# MCU.net
KiCad netlist of a schematic drawn in Altium Designer
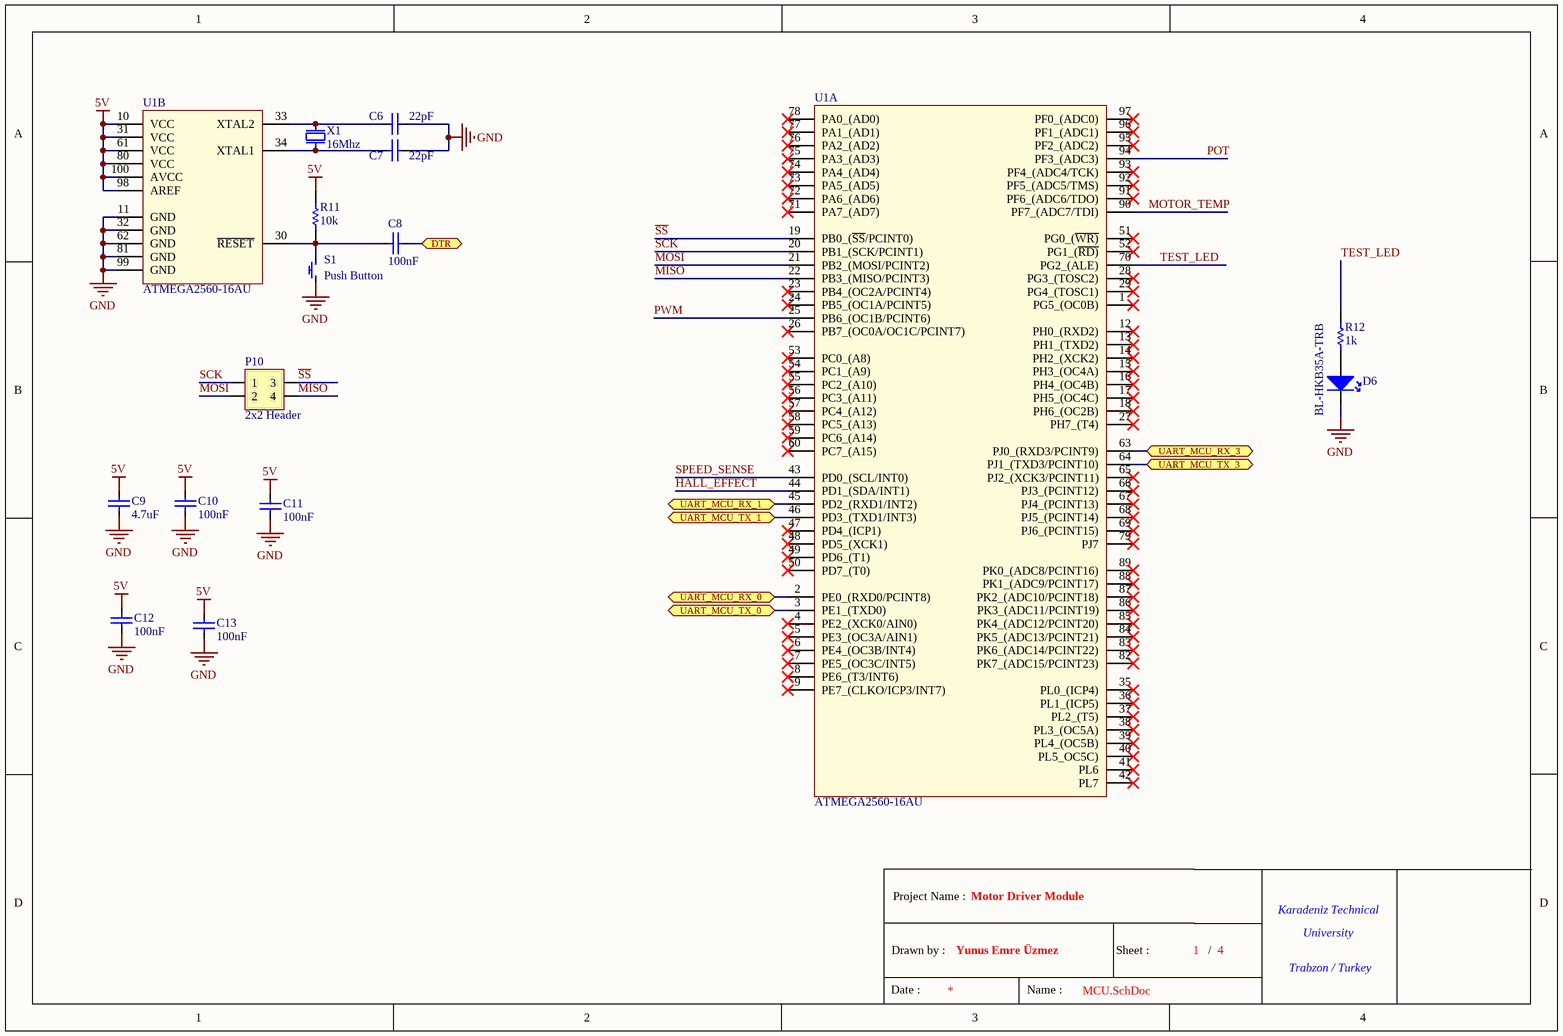
[diagram p0: MCU.SchDoc]

(export (version "E")
  (design (tool "Eeschema 10.0.6"))
  (components
    (comp (ref "C6")
      (value "22pF")
      (footprint "CAP-0805")
      (fields
        (field (name "MANUFACTURER") "Samsung Electro-Mechanics")
        (field (name "VOLTAGE") "50V")
        (field (name "TOLERANCE") "%5")
      )
      (libsource (lib "My_Libs") (part "CL21C220JBANNNC"))
    )
    (comp (ref "C7")
      (value "22pF")
      (footprint "CAP-0805")
      (fields
        (field (name "MANUFACTURER") "Samsung Electro-Mechanics")
        (field (name "VOLTAGE") "50V")
        (field (name "TOLERANCE") "%5")
      )
      (libsource (lib "My_Libs") (part "CL21C220JBANNNC"))
    )
    (comp (ref "C8")
      (value "100nF")
      (footprint "CAP-0603")
      (fields
        (field (name "MANUFACTURER") "TDK")
        (field (name "VOLTAGE") "50V")
        (field (name "TOLERANCE") "%10")
      )
      (libsource (lib "My_Libs") (part "CGA3E2X7R1H104K080AA"))
    )
    (comp (ref "C9")
      (value "4.7uF")
      (footprint "CAP-0805")
      (fields
        (field (name "MANUFACTURER") "Kemet")
        (field (name "VOLTAGE") "25V")
        (field (name "TOLERANCE") "%10")
      )
      (libsource (lib "My_Libs") (part "C0805C475K3RACAUTO"))
    )
    (comp (ref "C10")
      (value "100nF")
      (footprint "CAP-0603")
      (fields
        (field (name "MANUFACTURER") "TDK")
        (field (name "VOLTAGE") "50V")
        (field (name "TOLERANCE") "%10")
      )
      (libsource (lib "My_Libs") (part "CGA3E2X7R1H104K080AA"))
    )
    (comp (ref "C11")
      (value "100nF")
      (footprint "CAP-0603")
      (fields
        (field (name "MANUFACTURER") "TDK")
        (field (name "VOLTAGE") "50V")
        (field (name "TOLERANCE") "%10")
      )
      (libsource (lib "My_Libs") (part "CGA3E2X7R1H104K080AA"))
    )
    (comp (ref "C12")
      (value "100nF")
      (footprint "CAP-0603")
      (fields
        (field (name "MANUFACTURER") "TDK")
        (field (name "VOLTAGE") "50V")
        (field (name "TOLERANCE") "%10")
      )
      (libsource (lib "My_Libs") (part "CGA3E2X7R1H104K080AA"))
    )
    (comp (ref "C13")
      (value "100nF")
      (footprint "CAP-0603")
      (fields
        (field (name "MANUFACTURER") "TDK")
        (field (name "VOLTAGE") "50V")
        (field (name "TOLERANCE") "%10")
      )
      (libsource (lib "My_Libs") (part "CGA3E2X7R1H104K080AA"))
    )
    (comp (ref "D6")
      (value "BL-HKB35A-TRB")
      (footprint "LED-0805")
      (fields (field (name "MANUFACTURER") "BRIGHT LED"))
      (libsource (lib "My_Libs") (part "BL-HKB35A-TRB"))
    )
    (comp (ref "P10")
      (value "2x2 Header")
      (footprint "2x2 Header (2.54mm)")
      (libsource (lib "My_Libs") (part "2x2 Header (2.54mm)"))
    )
    (comp (ref "R11")
      (value "10k")
      (footprint "RES-0603")
      (fields
        (field (name "MANUFACTURER") "Vishay")
        (field (name "TOLERANCE") "%1")
        (field (name "POWER") "0.1W")
      )
      (libsource (lib "My_Libs") (part "CRCW060310K0FKEA"))
    )
    (comp (ref "R12")
      (value "1k")
      (footprint "RES-0603")
      (fields
        (field (name "MANUFACTURER") "Vishay")
        (field (name "TOLERANCE") "%1")
        (field (name "POWER") "0.1W")
      )
      (libsource (lib "My_Libs") (part "CRCW06031K00FKEAC"))
    )
    (comp (ref "S1")
      (value "Push Button")
      (footprint "2.54mm_Push Button")
      (libsource (lib "My_Libs") (part "Push Button"))
    )
    (comp (ref "U1")
      (value "ATMEGA2560-16AU")
      (footprint "Motor_Driver:TQFP-100 Microchip")
      (fields (field (name "MANUFACTURER") "Microchip"))
      (libsource (lib "My_Libs") (part "ATMEGA2560-16AU"))
    )
    (comp (ref "X1")
      (value "16Mhz")
      (footprint "OSC-THT (11.5*5.00*3.60)")
      (fields (field (name "MANUFACTURER") "ANSEN"))
      (libsource (lib "My_Libs") (part "AS49S-16M-FC160F3"))
    )
  )
  (nets
    (net (code "1") (name "/DTR") (class "Default")
      (node (ref "C8") (pin "2") (pinfunction "2_2") (pintype "passive"))
    )
    (net (code "2") (name "/HALL_EFFECT") (class "Default")
      (node (ref "U1") (pin "44") (pinfunction "PD1_(SDA/INT1)_44") (pintype "passive"))
    )
    (net (code "3") (name "/MISO") (class "Default")
      (node (ref "P10") (pin "4") (pinfunction "4_4") (pintype "passive"))
      (node (ref "U1") (pin "22") (pinfunction "PB3_(MISO/PCINT3)_22") (pintype "passive"))
    )
    (net (code "4") (name "/MOSI") (class "Default")
      (node (ref "P10") (pin "2") (pinfunction "2_2") (pintype "passive"))
      (node (ref "U1") (pin "21") (pinfunction "PB2_(MOSI/PCINT2)_21") (pintype "passive"))
    )
    (net (code "5") (name "/MOTOR_TEMP") (class "Default")
      (node (ref "U1") (pin "90") (pinfunction "PF7_(ADC7/TDI)_90") (pintype "passive"))
    )
    (net (code "6") (name "/POT") (class "Default")
      (node (ref "U1") (pin "94") (pinfunction "PF3_(ADC3)_94") (pintype "passive"))
    )
    (net (code "7") (name "/PWM") (class "Default")
      (node (ref "U1") (pin "25") (pinfunction "PB6_(OC1B/PCINT6)_25") (pintype "passive"))
    )
    (net (code "8") (name "/SCK") (class "Default")
      (node (ref "P10") (pin "1") (pinfunction "1_1") (pintype "passive"))
      (node (ref "U1") (pin "20") (pinfunction "PB1_(SCK/PCINT1)_20") (pintype "passive"))
    )
    (net (code "9") (name "/SPEED_SENSE") (class "Default")
      (node (ref "U1") (pin "43") (pinfunction "PD0_(SCL/INT0)_43") (pintype "passive"))
    )
    (net (code "10") (name "/TEST_LED") (class "Default")
      (node (ref "R12") (pin "2") (pinfunction "2_2") (pintype "passive"))
      (node (ref "U1") (pin "70") (pinfunction "PG2_(ALE)_70") (pintype "passive"))
    )
    (net (code "11") (name "/UART_MCU_RX_0") (class "Default")
      (node (ref "U1") (pin "2") (pinfunction "PE0_(RXD0/PCINT8)_2") (pintype "passive"))
    )
    (net (code "12") (name "/UART_MCU_RX_1") (class "Default")
      (node (ref "U1") (pin "45") (pinfunction "PD2_(RXD1/INT2)_45") (pintype "passive"))
    )
    (net (code "13") (name "/UART_MCU_RX_3") (class "Default")
      (node (ref "U1") (pin "63") (pinfunction "PJ0_(RXD3/PCINT9)_63") (pintype "passive"))
    )
    (net (code "14") (name "/UART_MCU_TX_0") (class "Default")
      (node (ref "U1") (pin "3") (pinfunction "PE1_(TXD0)_3") (pintype "passive"))
    )
    (net (code "15") (name "/UART_MCU_TX_1") (class "Default")
      (node (ref "U1") (pin "46") (pinfunction "PD3_(TXD1/INT3)_46") (pintype "passive"))
    )
    (net (code "16") (name "/UART_MCU_TX_3") (class "Default")
      (node (ref "U1") (pin "64") (pinfunction "PJ1_(TXD3/PCINT10)_64") (pintype "passive"))
    )
    (net (code "17") (name "/~{SS}") (class "Default")
      (node (ref "P10") (pin "3") (pinfunction "3_3") (pintype "passive"))
      (node (ref "U1") (pin "19") (pinfunction "PB0_(~{SS}/PCINT0)_19") (pintype "passive"))
    )
    (net (code "18") (name "5V") (class "Default")
      (node (ref "C10") (pin "2") (pinfunction "2_2") (pintype "passive"))
      (node (ref "C11") (pin "2") (pinfunction "2_2") (pintype "passive"))
      (node (ref "C12") (pin "2") (pinfunction "2_2") (pintype "passive"))
      (node (ref "C13") (pin "2") (pinfunction "2_2") (pintype "passive"))
      (node (ref "C9") (pin "2") (pinfunction "2_2") (pintype "passive"))
      (node (ref "R11") (pin "2") (pinfunction "2_2") (pintype "passive"))
      (node (ref "U1") (pin "10") (pinfunction "VCC_10") (pintype "passive"))
      (node (ref "U1") (pin "100") (pinfunction "AVCC_100") (pintype "passive"))
      (node (ref "U1") (pin "31") (pinfunction "VCC_31") (pintype "passive"))
      (node (ref "U1") (pin "61") (pinfunction "VCC_61") (pintype "passive"))
      (node (ref "U1") (pin "80") (pinfunction "VCC_80") (pintype "passive"))
      (node (ref "U1") (pin "98") (pinfunction "AREF_98") (pintype "passive"))
    )
    (net (code "19") (name "GND") (class "Default")
      (node (ref "C10") (pin "1") (pinfunction "1_1") (pintype "passive"))
      (node (ref "C11") (pin "1") (pinfunction "1_1") (pintype "passive"))
      (node (ref "C12") (pin "1") (pinfunction "1_1") (pintype "passive"))
      (node (ref "C13") (pin "1") (pinfunction "1_1") (pintype "passive"))
      (node (ref "C6") (pin "1") (pinfunction "1_1") (pintype "passive"))
      (node (ref "C7") (pin "1") (pinfunction "1_1") (pintype "passive"))
      (node (ref "C9") (pin "1") (pinfunction "1_1") (pintype "passive"))
      (node (ref "D6") (pin "2") (pinfunction "K_2") (pintype "passive"))
      (node (ref "S1") (pin "1") (pinfunction "1_1") (pintype "passive"))
      (node (ref "U1") (pin "11") (pinfunction "GND_11") (pintype "passive"))
      (node (ref "U1") (pin "32") (pinfunction "GND_32") (pintype "passive"))
      (node (ref "U1") (pin "62") (pinfunction "GND_62") (pintype "passive"))
      (node (ref "U1") (pin "81") (pinfunction "GND_81") (pintype "passive"))
      (node (ref "U1") (pin "99") (pinfunction "GND_99") (pintype "passive"))
    )
    (net (code "20") (name "Net-(D6-A)") (class "Default")
      (node (ref "D6") (pin "1") (pinfunction "A_1") (pintype "passive"))
      (node (ref "R12") (pin "1") (pinfunction "1_1") (pintype "passive"))
    )
    (net (code "21") (name "Net-(U1B-XTAL1)") (class "Default")
      (node (ref "C7") (pin "2") (pinfunction "2_2") (pintype "passive"))
      (node (ref "U1") (pin "34") (pinfunction "XTAL1_34") (pintype "passive"))
      (node (ref "X1") (pin "1") (pinfunction "1_1") (pintype "passive"))
    )
    (net (code "22") (name "Net-(U1B-XTAL2)") (class "Default")
      (node (ref "C6") (pin "2") (pinfunction "2_2") (pintype "passive"))
      (node (ref "U1") (pin "33") (pinfunction "XTAL2_33") (pintype "passive"))
      (node (ref "X1") (pin "2") (pinfunction "2_2") (pintype "passive"))
    )
    (net (code "23") (name "Net-(U1B-~{RESET})") (class "Default")
      (node (ref "C8") (pin "1") (pinfunction "1_1") (pintype "passive"))
      (node (ref "R11") (pin "1") (pinfunction "1_1") (pintype "passive"))
      (node (ref "S1") (pin "2") (pinfunction "2_2") (pintype "passive"))
      (node (ref "U1") (pin "30") (pinfunction "~{RESET}_30") (pintype "passive"))
    )
    (net (code "24") (name "unconnected-(U1A-PA0_(AD0)-Pad78)") (class "Default")
      (node (ref "U1") (pin "78") (pinfunction "PA0_(AD0)_78") (pintype "passive+no_connect"))
    )
    (net (code "25") (name "unconnected-(U1A-PA1_(AD1)-Pad77)") (class "Default")
      (node (ref "U1") (pin "77") (pinfunction "PA1_(AD1)_77") (pintype "passive+no_connect"))
    )
    (net (code "26") (name "unconnected-(U1A-PA2_(AD2)-Pad76)") (class "Default")
      (node (ref "U1") (pin "76") (pinfunction "PA2_(AD2)_76") (pintype "passive+no_connect"))
    )
    (net (code "27") (name "unconnected-(U1A-PA3_(AD3)-Pad75)") (class "Default")
      (node (ref "U1") (pin "75") (pinfunction "PA3_(AD3)_75") (pintype "passive+no_connect"))
    )
    (net (code "28") (name "unconnected-(U1A-PA4_(AD4)-Pad74)") (class "Default")
      (node (ref "U1") (pin "74") (pinfunction "PA4_(AD4)_74") (pintype "passive+no_connect"))
    )
    (net (code "29") (name "unconnected-(U1A-PA5_(AD5)-Pad73)") (class "Default")
      (node (ref "U1") (pin "73") (pinfunction "PA5_(AD5)_73") (pintype "passive+no_connect"))
    )
    (net (code "30") (name "unconnected-(U1A-PA6_(AD6)-Pad72)") (class "Default")
      (node (ref "U1") (pin "72") (pinfunction "PA6_(AD6)_72") (pintype "passive+no_connect"))
    )
    (net (code "31") (name "unconnected-(U1A-PA7_(AD7)-Pad71)") (class "Default")
      (node (ref "U1") (pin "71") (pinfunction "PA7_(AD7)_71") (pintype "passive+no_connect"))
    )
    (net (code "32") (name "unconnected-(U1A-PB4_(OC2A{slash}PCINT4)-Pad23)") (class "Default")
      (node (ref "U1") (pin "23") (pinfunction "PB4_(OC2A/PCINT4)_23") (pintype "passive+no_connect"))
    )
    (net (code "33") (name "unconnected-(U1A-PB5_(OC1A{slash}PCINT5)-Pad24)") (class "Default")
      (node (ref "U1") (pin "24") (pinfunction "PB5_(OC1A/PCINT5)_24") (pintype "passive+no_connect"))
    )
    (net (code "34") (name "unconnected-(U1A-PB7_(OC0A{slash}OC1C{slash}PCINT7)-Pad26)") (class "Default")
      (node (ref "U1") (pin "26") (pinfunction "PB7_(OC0A/OC1C/PCINT7)_26") (pintype "passive+no_connect"))
    )
    (net (code "35") (name "unconnected-(U1A-PC0_(A8)-Pad53)") (class "Default")
      (node (ref "U1") (pin "53") (pinfunction "PC0_(A8)_53") (pintype "passive+no_connect"))
    )
    (net (code "36") (name "unconnected-(U1A-PC1_(A9)-Pad54)") (class "Default")
      (node (ref "U1") (pin "54") (pinfunction "PC1_(A9)_54") (pintype "passive+no_connect"))
    )
    (net (code "37") (name "unconnected-(U1A-PC2_(A10)-Pad55)") (class "Default")
      (node (ref "U1") (pin "55") (pinfunction "PC2_(A10)_55") (pintype "passive+no_connect"))
    )
    (net (code "38") (name "unconnected-(U1A-PC3_(A11)-Pad56)") (class "Default")
      (node (ref "U1") (pin "56") (pinfunction "PC3_(A11)_56") (pintype "passive+no_connect"))
    )
    (net (code "39") (name "unconnected-(U1A-PC4_(A12)-Pad57)") (class "Default")
      (node (ref "U1") (pin "57") (pinfunction "PC4_(A12)_57") (pintype "passive+no_connect"))
    )
    (net (code "40") (name "unconnected-(U1A-PC5_(A13)-Pad58)") (class "Default")
      (node (ref "U1") (pin "58") (pinfunction "PC5_(A13)_58") (pintype "passive+no_connect"))
    )
    (net (code "41") (name "unconnected-(U1A-PC6_(A14)-Pad59)") (class "Default")
      (node (ref "U1") (pin "59") (pinfunction "PC6_(A14)_59") (pintype "passive+no_connect"))
    )
    (net (code "42") (name "unconnected-(U1A-PC7_(A15)-Pad60)") (class "Default")
      (node (ref "U1") (pin "60") (pinfunction "PC7_(A15)_60") (pintype "passive+no_connect"))
    )
    (net (code "43") (name "unconnected-(U1A-PD4_(ICP1)-Pad47)") (class "Default")
      (node (ref "U1") (pin "47") (pinfunction "PD4_(ICP1)_47") (pintype "passive+no_connect"))
    )
    (net (code "44") (name "unconnected-(U1A-PD5_(XCK1)-Pad48)") (class "Default")
      (node (ref "U1") (pin "48") (pinfunction "PD5_(XCK1)_48") (pintype "passive+no_connect"))
    )
    (net (code "45") (name "unconnected-(U1A-PD6_(T1)-Pad49)") (class "Default")
      (node (ref "U1") (pin "49") (pinfunction "PD6_(T1)_49") (pintype "passive+no_connect"))
    )
    (net (code "46") (name "unconnected-(U1A-PD7_(T0)-Pad50)") (class "Default")
      (node (ref "U1") (pin "50") (pinfunction "PD7_(T0)_50") (pintype "passive+no_connect"))
    )
    (net (code "47") (name "unconnected-(U1A-PE2_(XCK0{slash}AIN0)-Pad4)") (class "Default")
      (node (ref "U1") (pin "4") (pinfunction "PE2_(XCK0/AIN0)_4") (pintype "passive+no_connect"))
    )
    (net (code "48") (name "unconnected-(U1A-PE3_(OC3A{slash}AIN1)-Pad5)") (class "Default")
      (node (ref "U1") (pin "5") (pinfunction "PE3_(OC3A/AIN1)_5") (pintype "passive+no_connect"))
    )
    (net (code "49") (name "unconnected-(U1A-PE4_(OC3B{slash}INT4)-Pad6)") (class "Default")
      (node (ref "U1") (pin "6") (pinfunction "PE4_(OC3B/INT4)_6") (pintype "passive+no_connect"))
    )
    (net (code "50") (name "unconnected-(U1A-PE5_(OC3C{slash}INT5)-Pad7)") (class "Default")
      (node (ref "U1") (pin "7") (pinfunction "PE5_(OC3C/INT5)_7") (pintype "passive+no_connect"))
    )
    (net (code "51") (name "unconnected-(U1A-PE6_(T3{slash}INT6)-Pad8)") (class "Default")
      (node (ref "U1") (pin "8") (pinfunction "PE6_(T3/INT6)_8") (pintype "passive+no_connect"))
    )
    (net (code "52") (name "unconnected-(U1A-PE7_(CLKO{slash}ICP3{slash}INT7)-Pad9)") (class "Default")
      (node (ref "U1") (pin "9") (pinfunction "PE7_(CLKO/ICP3/INT7)_9") (pintype "passive+no_connect"))
    )
    (net (code "53") (name "unconnected-(U1A-PF0_(ADC0)-Pad97)") (class "Default")
      (node (ref "U1") (pin "97") (pinfunction "PF0_(ADC0)_97") (pintype "passive+no_connect"))
    )
    (net (code "54") (name "unconnected-(U1A-PF1_(ADC1)-Pad96)") (class "Default")
      (node (ref "U1") (pin "96") (pinfunction "PF1_(ADC1)_96") (pintype "passive+no_connect"))
    )
    (net (code "55") (name "unconnected-(U1A-PF2_(ADC2)-Pad95)") (class "Default")
      (node (ref "U1") (pin "95") (pinfunction "PF2_(ADC2)_95") (pintype "passive+no_connect"))
    )
    (net (code "56") (name "unconnected-(U1A-PF4_(ADC4{slash}TCK)-Pad93)") (class "Default")
      (node (ref "U1") (pin "93") (pinfunction "PF4_(ADC4/TCK)_93") (pintype "passive+no_connect"))
    )
    (net (code "57") (name "unconnected-(U1A-PF5_(ADC5{slash}TMS)-Pad92)") (class "Default")
      (node (ref "U1") (pin "92") (pinfunction "PF5_(ADC5/TMS)_92") (pintype "passive+no_connect"))
    )
    (net (code "58") (name "unconnected-(U1A-PF6_(ADC6{slash}TDO)-Pad91)") (class "Default")
      (node (ref "U1") (pin "91") (pinfunction "PF6_(ADC6/TDO)_91") (pintype "passive+no_connect"))
    )
    (net (code "59") (name "unconnected-(U1A-PG0_(~{WR)}-Pad51)") (class "Default")
      (node (ref "U1") (pin "51") (pinfunction "PG0_(~{WR)}_51") (pintype "passive+no_connect"))
    )
    (net (code "60") (name "unconnected-(U1A-PG1_(~{RD)}-Pad52)") (class "Default")
      (node (ref "U1") (pin "52") (pinfunction "PG1_(~{RD)}_52") (pintype "passive+no_connect"))
    )
    (net (code "61") (name "unconnected-(U1A-PG3_(TOSC2)-Pad28)") (class "Default")
      (node (ref "U1") (pin "28") (pinfunction "PG3_(TOSC2)_28") (pintype "passive+no_connect"))
    )
    (net (code "62") (name "unconnected-(U1A-PG4_(TOSC1)-Pad29)") (class "Default")
      (node (ref "U1") (pin "29") (pinfunction "PG4_(TOSC1)_29") (pintype "passive+no_connect"))
    )
    (net (code "63") (name "unconnected-(U1A-PG5_(OC0B)-Pad1)") (class "Default")
      (node (ref "U1") (pin "1") (pinfunction "PG5_(OC0B)_1") (pintype "passive+no_connect"))
    )
    (net (code "64") (name "unconnected-(U1A-PH0_(RXD2)-Pad12)") (class "Default")
      (node (ref "U1") (pin "12") (pinfunction "PH0_(RXD2)_12") (pintype "passive+no_connect"))
    )
    (net (code "65") (name "unconnected-(U1A-PH1_(TXD2)-Pad13)") (class "Default")
      (node (ref "U1") (pin "13") (pinfunction "PH1_(TXD2)_13") (pintype "passive+no_connect"))
    )
    (net (code "66") (name "unconnected-(U1A-PH2_(XCK2)-Pad14)") (class "Default")
      (node (ref "U1") (pin "14") (pinfunction "PH2_(XCK2)_14") (pintype "passive+no_connect"))
    )
    (net (code "67") (name "unconnected-(U1A-PH3_(OC4A)-Pad15)") (class "Default")
      (node (ref "U1") (pin "15") (pinfunction "PH3_(OC4A)_15") (pintype "passive+no_connect"))
    )
    (net (code "68") (name "unconnected-(U1A-PH4_(OC4B)-Pad16)") (class "Default")
      (node (ref "U1") (pin "16") (pinfunction "PH4_(OC4B)_16") (pintype "passive+no_connect"))
    )
    (net (code "69") (name "unconnected-(U1A-PH5_(OC4C)-Pad17)") (class "Default")
      (node (ref "U1") (pin "17") (pinfunction "PH5_(OC4C)_17") (pintype "passive+no_connect"))
    )
    (net (code "70") (name "unconnected-(U1A-PH6_(OC2B)-Pad18)") (class "Default")
      (node (ref "U1") (pin "18") (pinfunction "PH6_(OC2B)_18") (pintype "passive+no_connect"))
    )
    (net (code "71") (name "unconnected-(U1A-PH7_(T4)-Pad27)") (class "Default")
      (node (ref "U1") (pin "27") (pinfunction "PH7_(T4)_27") (pintype "passive+no_connect"))
    )
    (net (code "72") (name "unconnected-(U1A-PJ2_(XCK3{slash}PCINT11)-Pad65)") (class "Default")
      (node (ref "U1") (pin "65") (pinfunction "PJ2_(XCK3/PCINT11)_65") (pintype "passive+no_connect"))
    )
    (net (code "73") (name "unconnected-(U1A-PJ3_(PCINT12)-Pad66)") (class "Default")
      (node (ref "U1") (pin "66") (pinfunction "PJ3_(PCINT12)_66") (pintype "passive+no_connect"))
    )
    (net (code "74") (name "unconnected-(U1A-PJ4_(PCINT13)-Pad67)") (class "Default")
      (node (ref "U1") (pin "67") (pinfunction "PJ4_(PCINT13)_67") (pintype "passive+no_connect"))
    )
    (net (code "75") (name "unconnected-(U1A-PJ5_(PCINT14)-Pad68)") (class "Default")
      (node (ref "U1") (pin "68") (pinfunction "PJ5_(PCINT14)_68") (pintype "passive+no_connect"))
    )
    (net (code "76") (name "unconnected-(U1A-PJ6_(PCINT15)-Pad69)") (class "Default")
      (node (ref "U1") (pin "69") (pinfunction "PJ6_(PCINT15)_69") (pintype "passive+no_connect"))
    )
    (net (code "77") (name "unconnected-(U1A-PJ7-Pad79)") (class "Default")
      (node (ref "U1") (pin "79") (pinfunction "PJ7_79") (pintype "passive+no_connect"))
    )
    (net (code "78") (name "unconnected-(U1A-PK0_(ADC8{slash}PCINT16)-Pad89)") (class "Default")
      (node (ref "U1") (pin "89") (pinfunction "PK0_(ADC8/PCINT16)_89") (pintype "passive+no_connect"))
    )
    (net (code "79") (name "unconnected-(U1A-PK1_(ADC9{slash}PCINT17)-Pad88)") (class "Default")
      (node (ref "U1") (pin "88") (pinfunction "PK1_(ADC9/PCINT17)_88") (pintype "passive+no_connect"))
    )
    (net (code "80") (name "unconnected-(U1A-PK2_(ADC10{slash}PCINT18)-Pad87)") (class "Default")
      (node (ref "U1") (pin "87") (pinfunction "PK2_(ADC10/PCINT18)_87") (pintype "passive+no_connect"))
    )
    (net (code "81") (name "unconnected-(U1A-PK3_(ADC11{slash}PCINT19)-Pad86)") (class "Default")
      (node (ref "U1") (pin "86") (pinfunction "PK3_(ADC11/PCINT19)_86") (pintype "passive+no_connect"))
    )
    (net (code "82") (name "unconnected-(U1A-PK4_(ADC12{slash}PCINT20)-Pad85)") (class "Default")
      (node (ref "U1") (pin "85") (pinfunction "PK4_(ADC12/PCINT20)_85") (pintype "passive+no_connect"))
    )
    (net (code "83") (name "unconnected-(U1A-PK5_(ADC13{slash}PCINT21)-Pad84)") (class "Default")
      (node (ref "U1") (pin "84") (pinfunction "PK5_(ADC13/PCINT21)_84") (pintype "passive+no_connect"))
    )
    (net (code "84") (name "unconnected-(U1A-PK6_(ADC14{slash}PCINT22)-Pad83)") (class "Default")
      (node (ref "U1") (pin "83") (pinfunction "PK6_(ADC14/PCINT22)_83") (pintype "passive+no_connect"))
    )
    (net (code "85") (name "unconnected-(U1A-PK7_(ADC15{slash}PCINT23)-Pad82)") (class "Default")
      (node (ref "U1") (pin "82") (pinfunction "PK7_(ADC15/PCINT23)_82") (pintype "passive+no_connect"))
    )
    (net (code "86") (name "unconnected-(U1A-PL0_(ICP4)-Pad35)") (class "Default")
      (node (ref "U1") (pin "35") (pinfunction "PL0_(ICP4)_35") (pintype "passive+no_connect"))
    )
    (net (code "87") (name "unconnected-(U1A-PL1_(ICP5)-Pad36)") (class "Default")
      (node (ref "U1") (pin "36") (pinfunction "PL1_(ICP5)_36") (pintype "passive+no_connect"))
    )
    (net (code "88") (name "unconnected-(U1A-PL2_(T5)-Pad37)") (class "Default")
      (node (ref "U1") (pin "37") (pinfunction "PL2_(T5)_37") (pintype "passive+no_connect"))
    )
    (net (code "89") (name "unconnected-(U1A-PL3_(OC5A)-Pad38)") (class "Default")
      (node (ref "U1") (pin "38") (pinfunction "PL3_(OC5A)_38") (pintype "passive+no_connect"))
    )
    (net (code "90") (name "unconnected-(U1A-PL4_(OC5B)-Pad39)") (class "Default")
      (node (ref "U1") (pin "39") (pinfunction "PL4_(OC5B)_39") (pintype "passive+no_connect"))
    )
    (net (code "91") (name "unconnected-(U1A-PL5_OC5C)-Pad40)") (class "Default")
      (node (ref "U1") (pin "40") (pinfunction "PL5_OC5C)_40") (pintype "passive+no_connect"))
    )
    (net (code "92") (name "unconnected-(U1A-PL6-Pad41)") (class "Default")
      (node (ref "U1") (pin "41") (pinfunction "PL6_41") (pintype "passive+no_connect"))
    )
    (net (code "93") (name "unconnected-(U1A-PL7-Pad42)") (class "Default")
      (node (ref "U1") (pin "42") (pinfunction "PL7_42") (pintype "passive+no_connect"))
    )
  )
)
